# ProPrj_EPM_PCB.net
KiCad netlist of a schematic drawn in EasyEDA Pro
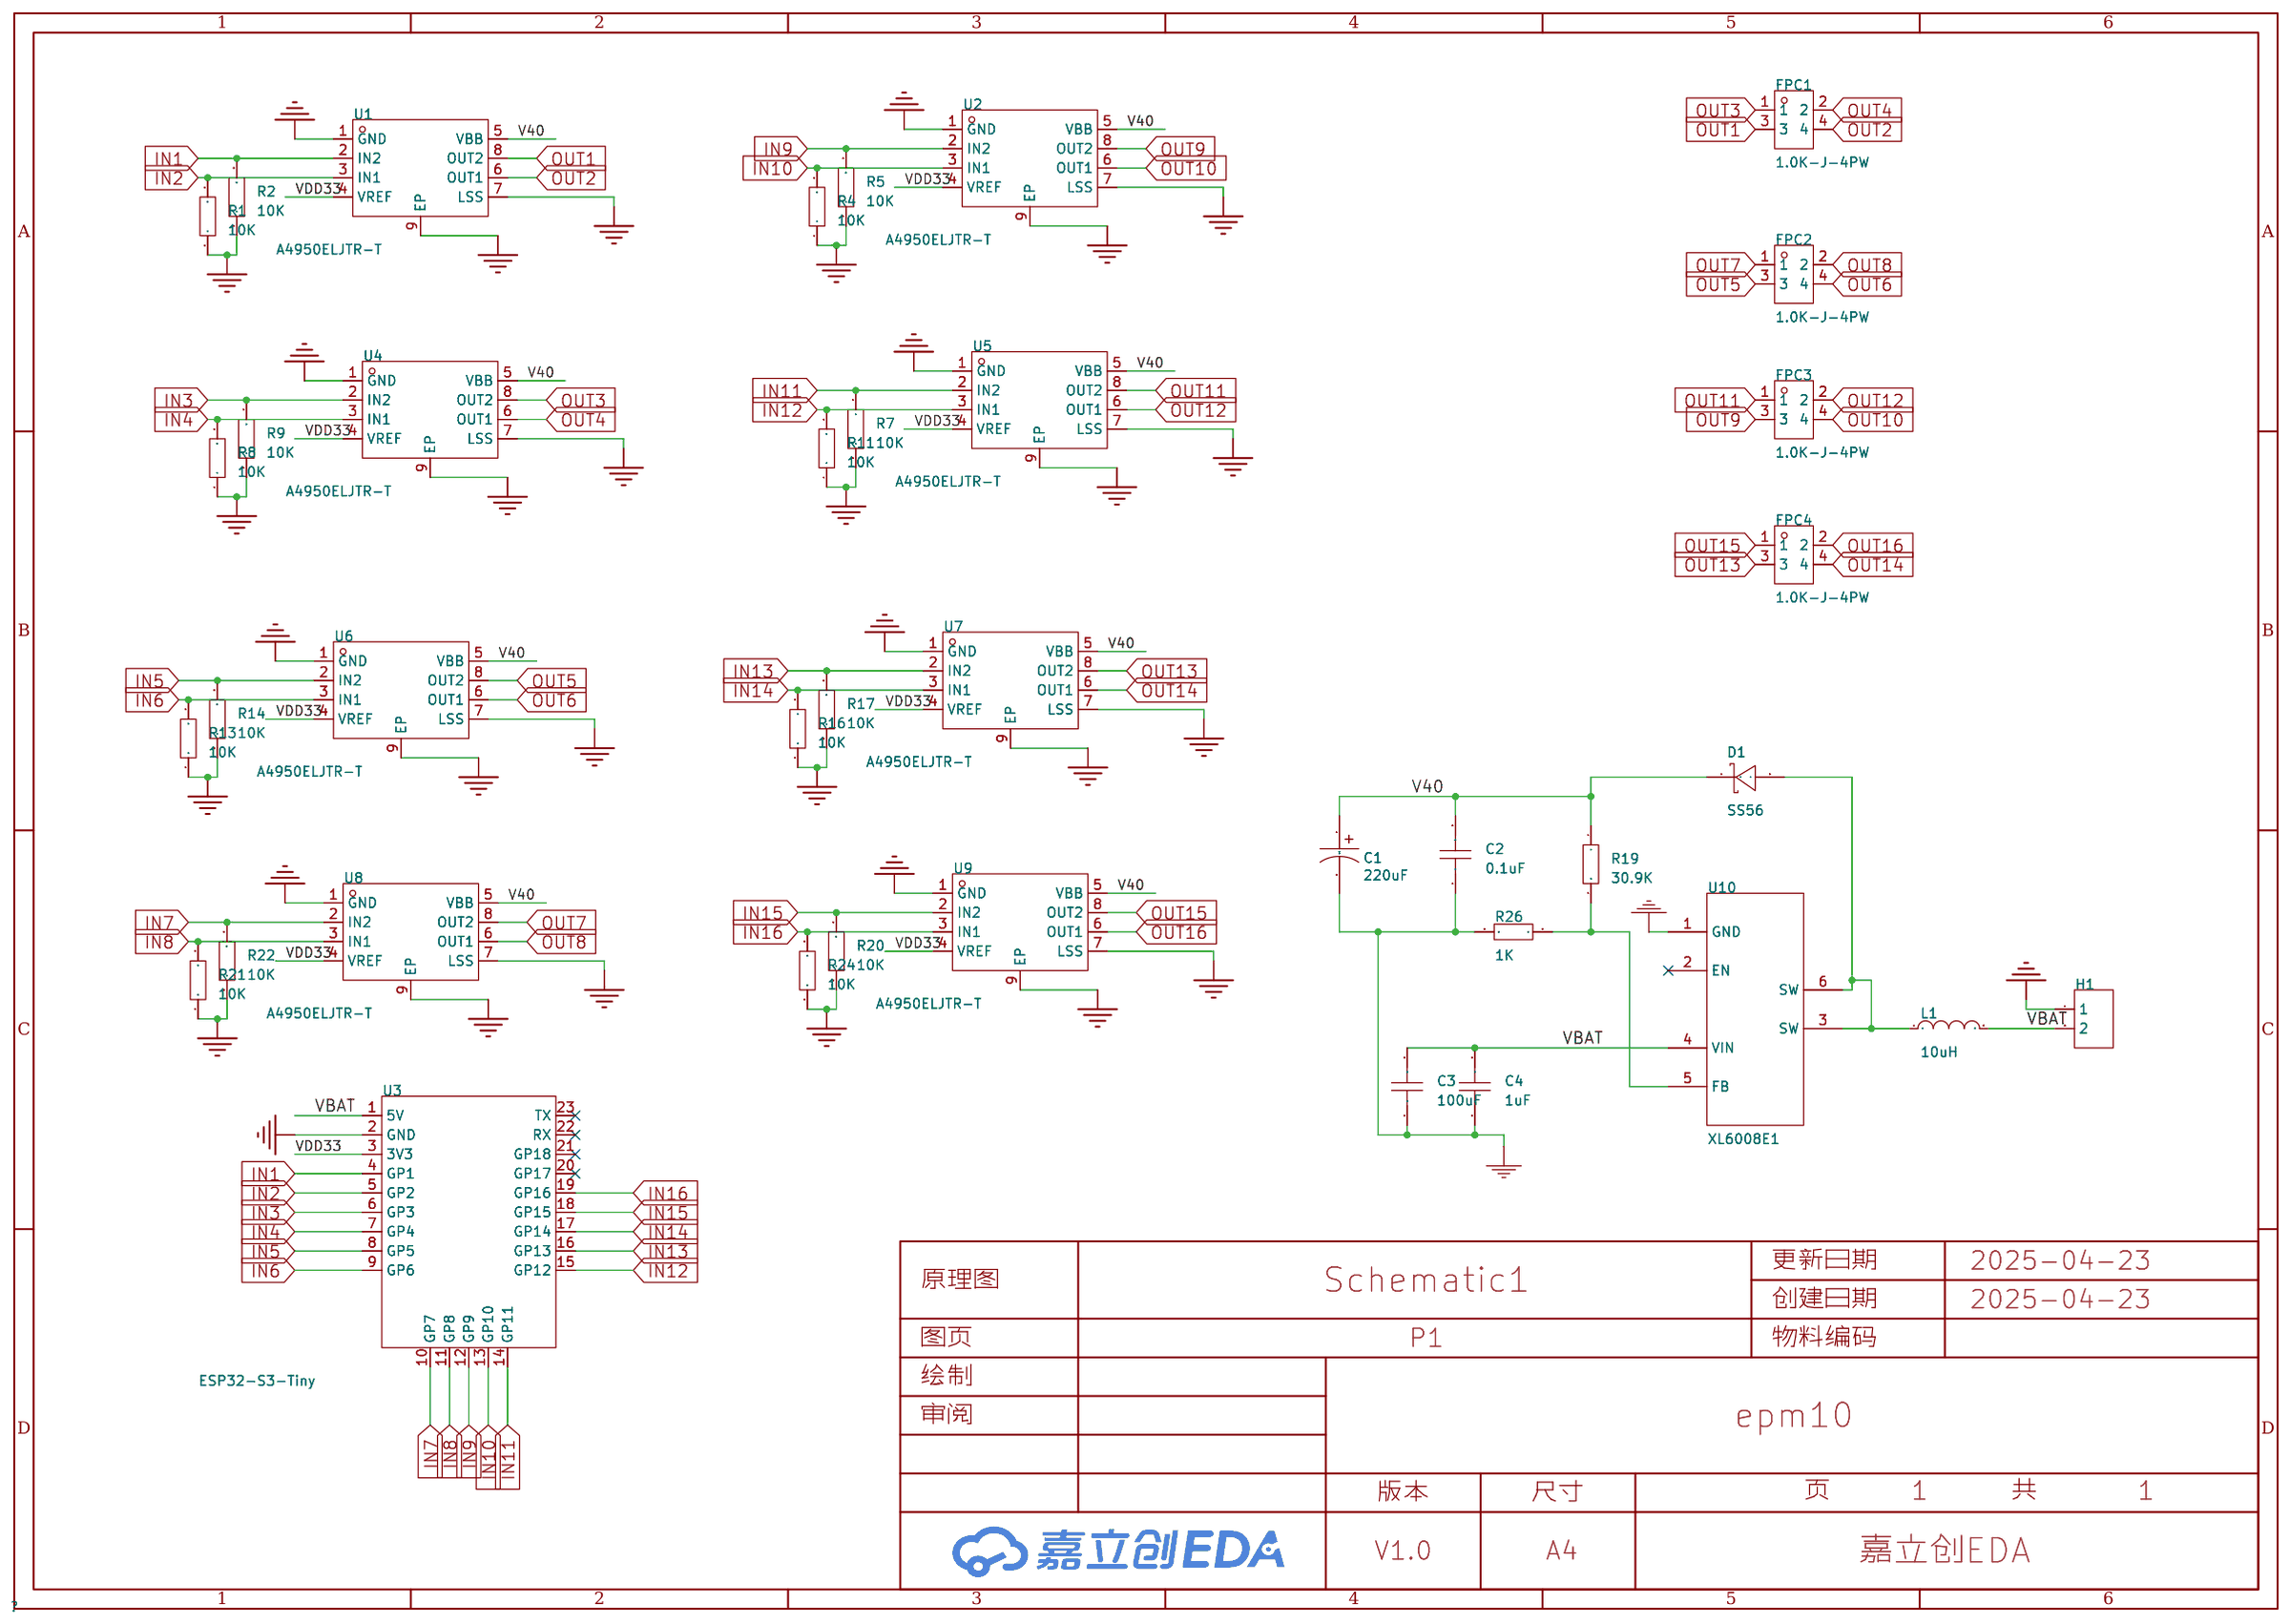
[diagram p0: schematic sheet]

(export (version "E")
  (design (tool "Eeschema 10.0.6"))
  (components
    (comp (ref "C1")
      (value "220uF")
      (footprint "easyedapro:CAP-TH_BD10.0-P5.00-D0.6-FD-A")
      (fields
        (field (name "Manufacturer Part") "SPZ1JM221G15O00RAXXX")
        (field (name "Manufacturer") "AISHI(艾华集团)")
      )
      (libsource (lib "easyedapro") (part "220uF"))
    )
    (comp (ref "C2")
      (value "0.1uF")
      (footprint "easyedapro:C0603")
      (libsource (lib "easyedapro") (part "CapAcitance"))
    )
    (comp (ref "C3")
      (value "100uF")
      (footprint "easyedapro:C1210")
      (description "容值:100uF;精度:±20%;额定电压:10V;材质(温度系数):X5R;")
      (fields
        (field (name "Manufacturer Part") "GRM32ER61A107ME20L")
        (field (name "Manufacturer") "muRata(村田)")
      )
      (libsource (lib "easyedapro") (part "GRM32ER61A107ME20L"))
    )
    (comp (ref "C4")
      (value "1uF")
      (footprint "easyedapro:C0603")
      (libsource (lib "easyedapro") (part "CapAcitance"))
    )
    (comp (ref "D1")
      (value "SS56")
      (footprint "easyedapro:SMA_L4.3-W2.6-LS5.2-RD")
      (description "二极管配置:独立式;正向压降(Vf):700mV@5A;直流反向耐压(Vr):60V;整流电流:5A;")
      (fields (field (name "Manufacturer") "MDD(辰达半导体)"))
      (libsource (lib "easyedapro") (part "SS56"))
    )
    (comp (ref "FPC1")
      (value "1.0K-J-4PW")
      (footprint "easyedapro:FPC-TH_4P-P1.00_HDGC_1.0K-J-4PW")
      (description "锁定特性:抽屉式;触点类型:下接;触点数量:4P;间距:1mm;安装类型:弯插;工作温度范围:-20°C~+85°C;")
      (fields (field (name "Manufacturer") "HDGC(华德共创)"))
      (libsource (lib "easyedapro") (part "1.0K-J-4PW"))
    )
    (comp (ref "FPC2")
      (value "1.0K-J-4PW")
      (footprint "easyedapro:FPC-TH_4P-P1.00_HDGC_1.0K-J-4PW")
      (description "锁定特性:抽屉式;触点类型:下接;触点数量:4P;间距:1mm;安装类型:弯插;工作温度范围:-20°C~+85°C;")
      (fields (field (name "Manufacturer") "HDGC(华德共创)"))
      (libsource (lib "easyedapro") (part "1.0K-J-4PW"))
    )
    (comp (ref "FPC3")
      (value "1.0K-J-4PW")
      (footprint "easyedapro:FPC-TH_4P-P1.00_HDGC_1.0K-J-4PW")
      (description "锁定特性:抽屉式;触点类型:下接;触点数量:4P;间距:1mm;安装类型:弯插;工作温度范围:-20°C~+85°C;")
      (fields (field (name "Manufacturer") "HDGC(华德共创)"))
      (libsource (lib "easyedapro") (part "1.0K-J-4PW"))
    )
    (comp (ref "FPC4")
      (value "1.0K-J-4PW")
      (footprint "easyedapro:FPC-TH_4P-P1.00_HDGC_1.0K-J-4PW")
      (description "锁定特性:抽屉式;触点类型:下接;触点数量:4P;间距:1mm;安装类型:弯插;工作温度范围:-20°C~+85°C;")
      (fields (field (name "Manufacturer") "HDGC(华德共创)"))
      (libsource (lib "easyedapro") (part "1.0K-J-4PW"))
    )
    (comp (ref "H1")
      (value "~")
      (footprint "easyedapro:HDR-TH_2P-P2.54-V-F")
      (libsource (lib "easyedapro") (part "Header-Female-2.54_1x2"))
    )
    (comp (ref "L1")
      (value "10uH")
      (footprint "easyedapro:IND-SMD_L3.0-W3.0_FTC303020D")
      (description "电感值:10uH;精度:±20%;额定电流:2.5A;饱和电流(Isat):3.8A;类型:一体成型电感;")
      (fields
        (field (name "Manufacturer Part") "FTC303020D100MBCA")
        (field (name "Manufacturer") "cjiang(长江微电)")
      )
      (libsource (lib "easyedapro") (part "FTC303020D100MBCA"))
    )
    (comp (ref "R1") (value "10K") (footprint "easyedapro:R0603") (libsource (lib "easyedapro") (part "电阻")))
    (comp (ref "R2") (value "10K") (footprint "easyedapro:R0603") (libsource (lib "easyedapro") (part "电阻")))
    (comp (ref "R4") (value "10K") (footprint "easyedapro:R0603") (libsource (lib "easyedapro") (part "电阻")))
    (comp (ref "R5") (value "10K") (footprint "easyedapro:R0603") (libsource (lib "easyedapro") (part "电阻")))
    (comp (ref "R7") (value "10K") (footprint "easyedapro:R0603") (libsource (lib "easyedapro") (part "电阻")))
    (comp (ref "R8") (value "10K") (footprint "easyedapro:R0603") (libsource (lib "easyedapro") (part "电阻")))
    (comp (ref "R9") (value "10K") (footprint "easyedapro:R0603") (libsource (lib "easyedapro") (part "电阻")))
    (comp (ref "R11") (value "10K") (footprint "easyedapro:R0603") (libsource (lib "easyedapro") (part "电阻")))
    (comp (ref "R13") (value "10K") (footprint "easyedapro:R0603") (libsource (lib "easyedapro") (part "电阻")))
    (comp (ref "R14") (value "10K") (footprint "easyedapro:R0603") (libsource (lib "easyedapro") (part "电阻")))
    (comp (ref "R16") (value "10K") (footprint "easyedapro:R0603") (libsource (lib "easyedapro") (part "电阻")))
    (comp (ref "R17") (value "10K") (footprint "easyedapro:R0603") (libsource (lib "easyedapro") (part "电阻")))
    (comp (ref "R19")
      (value "30.9K")
      (footprint "easyedapro:R0603")
      (libsource (lib "easyedapro") (part "电阻"))
    )
    (comp (ref "R20") (value "10K") (footprint "easyedapro:R0603") (libsource (lib "easyedapro") (part "电阻")))
    (comp (ref "R21") (value "10K") (footprint "easyedapro:R0603") (libsource (lib "easyedapro") (part "电阻")))
    (comp (ref "R22") (value "10K") (footprint "easyedapro:R0603") (libsource (lib "easyedapro") (part "电阻")))
    (comp (ref "R24") (value "10K") (footprint "easyedapro:R0603") (libsource (lib "easyedapro") (part "电阻")))
    (comp (ref "R26") (value "1K") (footprint "easyedapro:R0603") (libsource (lib "easyedapro") (part "电阻")))
    (comp (ref "U1")
      (value "A4950ELJTR-T")
      (footprint "easyedapro:ESOP-8_L4.9-W3.9-P1.27-LS6.0-BL-EP-1")
      (description "全桥DMOS PWM电机驱动器，直流有刷电机")
      (fields (field (name "Manufacturer") "JSMSEMI(杰盛微)"))
      (libsource (lib "easyedapro") (part "A4950ELJTR-T_C5804620"))
    )
    (comp (ref "U2")
      (value "A4950ELJTR-T")
      (footprint "easyedapro:ESOP-8_L4.9-W3.9-P1.27-LS6.0-BL-EP-1")
      (description "全桥DMOS PWM电机驱动器，直流有刷电机")
      (fields (field (name "Manufacturer") "JSMSEMI(杰盛微)"))
      (libsource (lib "easyedapro") (part "A4950ELJTR-T_C5804620"))
    )
    (comp (ref "U3")
      (value "ESP32-S3-Tiny")
      (footprint "easyedapro:COMM-SMD_23P-P2.54-L23.5-W18.0_ESP32-S3-TINY")
      (libsource (lib "easyedapro") (part "ESP32-S3-TINY"))
    )
    (comp (ref "U4")
      (value "A4950ELJTR-T")
      (footprint "easyedapro:ESOP-8_L4.9-W3.9-P1.27-LS6.0-BL-EP-1")
      (description "全桥DMOS PWM电机驱动器，直流有刷电机")
      (fields (field (name "Manufacturer") "JSMSEMI(杰盛微)"))
      (libsource (lib "easyedapro") (part "A4950ELJTR-T_C5804620"))
    )
    (comp (ref "U5")
      (value "A4950ELJTR-T")
      (footprint "easyedapro:ESOP-8_L4.9-W3.9-P1.27-LS6.0-BL-EP-1")
      (description "全桥DMOS PWM电机驱动器，直流有刷电机")
      (fields (field (name "Manufacturer") "JSMSEMI(杰盛微)"))
      (libsource (lib "easyedapro") (part "A4950ELJTR-T_C5804620"))
    )
    (comp (ref "U6")
      (value "A4950ELJTR-T")
      (footprint "easyedapro:ESOP-8_L4.9-W3.9-P1.27-LS6.0-BL-EP-1")
      (description "全桥DMOS PWM电机驱动器，直流有刷电机")
      (fields (field (name "Manufacturer") "JSMSEMI(杰盛微)"))
      (libsource (lib "easyedapro") (part "A4950ELJTR-T_C5804620"))
    )
    (comp (ref "U7")
      (value "A4950ELJTR-T")
      (footprint "easyedapro:ESOP-8_L4.9-W3.9-P1.27-LS6.0-BL-EP-1")
      (description "全桥DMOS PWM电机驱动器，直流有刷电机")
      (fields (field (name "Manufacturer") "JSMSEMI(杰盛微)"))
      (libsource (lib "easyedapro") (part "A4950ELJTR-T_C5804620"))
    )
    (comp (ref "U8")
      (value "A4950ELJTR-T")
      (footprint "easyedapro:ESOP-8_L4.9-W3.9-P1.27-LS6.0-BL-EP-1")
      (description "全桥DMOS PWM电机驱动器，直流有刷电机")
      (fields (field (name "Manufacturer") "JSMSEMI(杰盛微)"))
      (libsource (lib "easyedapro") (part "A4950ELJTR-T_C5804620"))
    )
    (comp (ref "U9")
      (value "A4950ELJTR-T")
      (footprint "easyedapro:ESOP-8_L4.9-W3.9-P1.27-LS6.0-BL-EP-1")
      (description "全桥DMOS PWM电机驱动器，直流有刷电机")
      (fields (field (name "Manufacturer") "JSMSEMI(杰盛微)"))
      (libsource (lib "easyedapro") (part "A4950ELJTR-T_C5804620"))
    )
    (comp (ref "U10")
      (value "XL6008E1")
      (footprint "easyedapro:TO-252-5_L6.6-W5.8-P1.27-TL")
      (description "功能类型:升降压型;输入电压:3.6V~32V;输出电流(最大值):3A;")
      (fields (field (name "Manufacturer") "XLSEMI(芯龙)"))
      (libsource (lib "easyedapro") (part "XL6008E1_C73012"))
    )
  )
  (nets
    (net (code "1") (name "/V40") (class "Default")
      (node (ref "C1") (pin "1") (pinfunction "1_1") (pintype "unspecified"))
      (node (ref "C2") (pin "2") (pinfunction "2_2") (pintype "input"))
      (node (ref "D1") (pin "1") (pinfunction "K_1") (pintype "unspecified"))
      (node (ref "R19") (pin "1") (pinfunction "1_1") (pintype "input"))
      (node (ref "U1") (pin "5") (pinfunction "VBB_5") (pintype "unspecified"))
      (node (ref "U2") (pin "5") (pinfunction "VBB_5") (pintype "unspecified"))
      (node (ref "U4") (pin "5") (pinfunction "VBB_5") (pintype "unspecified"))
      (node (ref "U5") (pin "5") (pinfunction "VBB_5") (pintype "unspecified"))
      (node (ref "U6") (pin "5") (pinfunction "VBB_5") (pintype "unspecified"))
      (node (ref "U7") (pin "5") (pinfunction "VBB_5") (pintype "unspecified"))
      (node (ref "U8") (pin "5") (pinfunction "VBB_5") (pintype "unspecified"))
      (node (ref "U9") (pin "5") (pinfunction "VBB_5") (pintype "unspecified"))
    )
    (net (code "2") (name "/VBAT") (class "Default")
      (node (ref "C3") (pin "2") (pinfunction "2_2") (pintype "unspecified"))
      (node (ref "C4") (pin "2") (pinfunction "2_2") (pintype "input"))
      (node (ref "H1") (pin "2") (pinfunction "2_2") (pintype "input"))
      (node (ref "L1") (pin "2") (pinfunction "2_2") (pintype "unspecified"))
      (node (ref "U10") (pin "4") (pinfunction "VIN_4") (pintype "unspecified"))
      (node (ref "U3") (pin "1") (pinfunction "5V_1") (pintype "unspecified"))
    )
    (net (code "3") (name "/VDD33") (class "Default")
      (node (ref "U1") (pin "4") (pinfunction "VREF_4") (pintype "unspecified"))
      (node (ref "U2") (pin "4") (pinfunction "VREF_4") (pintype "unspecified"))
      (node (ref "U3") (pin "3") (pinfunction "3V3_3") (pintype "unspecified"))
      (node (ref "U4") (pin "4") (pinfunction "VREF_4") (pintype "unspecified"))
      (node (ref "U5") (pin "4") (pinfunction "VREF_4") (pintype "unspecified"))
      (node (ref "U6") (pin "4") (pinfunction "VREF_4") (pintype "unspecified"))
      (node (ref "U7") (pin "4") (pinfunction "VREF_4") (pintype "unspecified"))
      (node (ref "U8") (pin "4") (pinfunction "VREF_4") (pintype "unspecified"))
      (node (ref "U9") (pin "4") (pinfunction "VREF_4") (pintype "unspecified"))
    )
    (net (code "4") (name "GND") (class "Default")
      (node (ref "C1") (pin "2") (pinfunction "2_2") (pintype "unspecified"))
      (node (ref "C2") (pin "1") (pinfunction "1_1") (pintype "input"))
      (node (ref "C3") (pin "1") (pinfunction "1_1") (pintype "unspecified"))
      (node (ref "C4") (pin "1") (pinfunction "1_1") (pintype "input"))
      (node (ref "H1") (pin "1") (pinfunction "1_1") (pintype "input"))
      (node (ref "R1") (pin "1") (pinfunction "1_1") (pintype "input"))
      (node (ref "R11") (pin "1") (pinfunction "1_1") (pintype "input"))
      (node (ref "R13") (pin "1") (pinfunction "1_1") (pintype "input"))
      (node (ref "R14") (pin "1") (pinfunction "1_1") (pintype "input"))
      (node (ref "R16") (pin "1") (pinfunction "1_1") (pintype "input"))
      (node (ref "R17") (pin "1") (pinfunction "1_1") (pintype "input"))
      (node (ref "R2") (pin "1") (pinfunction "1_1") (pintype "input"))
      (node (ref "R20") (pin "1") (pinfunction "1_1") (pintype "input"))
      (node (ref "R21") (pin "1") (pinfunction "1_1") (pintype "input"))
      (node (ref "R22") (pin "1") (pinfunction "1_1") (pintype "input"))
      (node (ref "R24") (pin "1") (pinfunction "1_1") (pintype "input"))
      (node (ref "R26") (pin "2") (pinfunction "2_2") (pintype "input"))
      (node (ref "R4") (pin "1") (pinfunction "1_1") (pintype "input"))
      (node (ref "R5") (pin "1") (pinfunction "1_1") (pintype "input"))
      (node (ref "R7") (pin "1") (pinfunction "1_1") (pintype "input"))
      (node (ref "R8") (pin "1") (pinfunction "1_1") (pintype "input"))
      (node (ref "R9") (pin "1") (pinfunction "1_1") (pintype "input"))
      (node (ref "U1") (pin "1") (pinfunction "GND_1") (pintype "unspecified"))
      (node (ref "U1") (pin "7") (pinfunction "LSS_7") (pintype "unspecified"))
      (node (ref "U1") (pin "9") (pinfunction "EP_9") (pintype "unspecified"))
      (node (ref "U10") (pin "1") (pinfunction "GND_1") (pintype "unspecified"))
      (node (ref "U2") (pin "1") (pinfunction "GND_1") (pintype "unspecified"))
      (node (ref "U2") (pin "7") (pinfunction "LSS_7") (pintype "unspecified"))
      (node (ref "U2") (pin "9") (pinfunction "EP_9") (pintype "unspecified"))
      (node (ref "U3") (pin "2") (pinfunction "GND_2") (pintype "unspecified"))
      (node (ref "U4") (pin "1") (pinfunction "GND_1") (pintype "unspecified"))
      (node (ref "U4") (pin "7") (pinfunction "LSS_7") (pintype "unspecified"))
      (node (ref "U4") (pin "9") (pinfunction "EP_9") (pintype "unspecified"))
      (node (ref "U5") (pin "1") (pinfunction "GND_1") (pintype "unspecified"))
      (node (ref "U5") (pin "7") (pinfunction "LSS_7") (pintype "unspecified"))
      (node (ref "U5") (pin "9") (pinfunction "EP_9") (pintype "unspecified"))
      (node (ref "U6") (pin "1") (pinfunction "GND_1") (pintype "unspecified"))
      (node (ref "U6") (pin "7") (pinfunction "LSS_7") (pintype "unspecified"))
      (node (ref "U6") (pin "9") (pinfunction "EP_9") (pintype "unspecified"))
      (node (ref "U7") (pin "1") (pinfunction "GND_1") (pintype "unspecified"))
      (node (ref "U7") (pin "7") (pinfunction "LSS_7") (pintype "unspecified"))
      (node (ref "U7") (pin "9") (pinfunction "EP_9") (pintype "unspecified"))
      (node (ref "U8") (pin "1") (pinfunction "GND_1") (pintype "unspecified"))
      (node (ref "U8") (pin "7") (pinfunction "LSS_7") (pintype "unspecified"))
      (node (ref "U8") (pin "9") (pinfunction "EP_9") (pintype "unspecified"))
      (node (ref "U9") (pin "1") (pinfunction "GND_1") (pintype "unspecified"))
      (node (ref "U9") (pin "7") (pinfunction "LSS_7") (pintype "unspecified"))
      (node (ref "U9") (pin "9") (pinfunction "EP_9") (pintype "unspecified"))
    )
    (net (code "5") (name "IN1") (class "Default")
      (node (ref "R2") (pin "2") (pinfunction "2_2") (pintype "input"))
      (node (ref "U1") (pin "2") (pinfunction "IN2_2") (pintype "unspecified"))
      (node (ref "U3") (pin "4") (pinfunction "GP1_4") (pintype "unspecified"))
    )
    (net (code "6") (name "IN2") (class "Default")
      (node (ref "R1") (pin "2") (pinfunction "2_2") (pintype "input"))
      (node (ref "U1") (pin "3") (pinfunction "IN1_3") (pintype "unspecified"))
      (node (ref "U3") (pin "5") (pinfunction "GP2_5") (pintype "unspecified"))
    )
    (net (code "7") (name "IN3") (class "Default")
      (node (ref "R9") (pin "2") (pinfunction "2_2") (pintype "input"))
      (node (ref "U3") (pin "6") (pinfunction "GP3_6") (pintype "unspecified"))
      (node (ref "U4") (pin "2") (pinfunction "IN2_2") (pintype "unspecified"))
    )
    (net (code "8") (name "IN4") (class "Default")
      (node (ref "R8") (pin "2") (pinfunction "2_2") (pintype "input"))
      (node (ref "U3") (pin "7") (pinfunction "GP4_7") (pintype "unspecified"))
      (node (ref "U4") (pin "3") (pinfunction "IN1_3") (pintype "unspecified"))
    )
    (net (code "9") (name "IN5") (class "Default")
      (node (ref "R14") (pin "2") (pinfunction "2_2") (pintype "input"))
      (node (ref "U3") (pin "8") (pinfunction "GP5_8") (pintype "unspecified"))
      (node (ref "U6") (pin "2") (pinfunction "IN2_2") (pintype "unspecified"))
    )
    (net (code "10") (name "IN6") (class "Default")
      (node (ref "R13") (pin "2") (pinfunction "2_2") (pintype "input"))
      (node (ref "U3") (pin "9") (pinfunction "GP6_9") (pintype "unspecified"))
      (node (ref "U6") (pin "3") (pinfunction "IN1_3") (pintype "unspecified"))
    )
    (net (code "11") (name "IN7") (class "Default")
      (node (ref "R22") (pin "2") (pinfunction "2_2") (pintype "input"))
      (node (ref "U3") (pin "10") (pinfunction "GP7_10") (pintype "unspecified"))
      (node (ref "U8") (pin "2") (pinfunction "IN2_2") (pintype "unspecified"))
    )
    (net (code "12") (name "IN8") (class "Default")
      (node (ref "R21") (pin "2") (pinfunction "2_2") (pintype "input"))
      (node (ref "U3") (pin "11") (pinfunction "GP8_11") (pintype "unspecified"))
      (node (ref "U8") (pin "3") (pinfunction "IN1_3") (pintype "unspecified"))
    )
    (net (code "13") (name "IN9") (class "Default")
      (node (ref "R5") (pin "2") (pinfunction "2_2") (pintype "input"))
      (node (ref "U2") (pin "2") (pinfunction "IN2_2") (pintype "unspecified"))
      (node (ref "U3") (pin "12") (pinfunction "GP9_12") (pintype "unspecified"))
    )
    (net (code "14") (name "IN10") (class "Default")
      (node (ref "R4") (pin "2") (pinfunction "2_2") (pintype "input"))
      (node (ref "U2") (pin "3") (pinfunction "IN1_3") (pintype "unspecified"))
      (node (ref "U3") (pin "13") (pinfunction "GP10_13") (pintype "unspecified"))
    )
    (net (code "15") (name "IN11") (class "Default")
      (node (ref "R7") (pin "2") (pinfunction "2_2") (pintype "input"))
      (node (ref "U3") (pin "14") (pinfunction "GP11_14") (pintype "unspecified"))
      (node (ref "U5") (pin "2") (pinfunction "IN2_2") (pintype "unspecified"))
    )
    (net (code "16") (name "IN12") (class "Default")
      (node (ref "R11") (pin "2") (pinfunction "2_2") (pintype "input"))
      (node (ref "U3") (pin "15") (pinfunction "GP12_15") (pintype "unspecified"))
      (node (ref "U5") (pin "3") (pinfunction "IN1_3") (pintype "unspecified"))
    )
    (net (code "17") (name "IN13") (class "Default")
      (node (ref "R17") (pin "2") (pinfunction "2_2") (pintype "input"))
      (node (ref "U3") (pin "16") (pinfunction "GP13_16") (pintype "unspecified"))
      (node (ref "U7") (pin "2") (pinfunction "IN2_2") (pintype "unspecified"))
    )
    (net (code "18") (name "IN14") (class "Default")
      (node (ref "R16") (pin "2") (pinfunction "2_2") (pintype "input"))
      (node (ref "U3") (pin "17") (pinfunction "GP14_17") (pintype "unspecified"))
      (node (ref "U7") (pin "3") (pinfunction "IN1_3") (pintype "unspecified"))
    )
    (net (code "19") (name "IN15") (class "Default")
      (node (ref "R20") (pin "2") (pinfunction "2_2") (pintype "input"))
      (node (ref "U3") (pin "18") (pinfunction "GP15_18") (pintype "unspecified"))
      (node (ref "U9") (pin "2") (pinfunction "IN2_2") (pintype "unspecified"))
    )
    (net (code "20") (name "IN16") (class "Default")
      (node (ref "R24") (pin "2") (pinfunction "2_2") (pintype "input"))
      (node (ref "U3") (pin "19") (pinfunction "GP16_19") (pintype "unspecified"))
      (node (ref "U9") (pin "3") (pinfunction "IN1_3") (pintype "unspecified"))
    )
    (net (code "21") (name "Net-(D1-A)") (class "Default")
      (node (ref "D1") (pin "2") (pinfunction "A_2") (pintype "unspecified"))
      (node (ref "L1") (pin "1") (pinfunction "1_1") (pintype "unspecified"))
      (node (ref "U10") (pin "3") (pinfunction "SW_3") (pintype "unspecified"))
      (node (ref "U10") (pin "6") (pinfunction "SW_6") (pintype "unspecified"))
    )
    (net (code "22") (name "Net-(U10-FB)") (class "Default")
      (node (ref "R19") (pin "2") (pinfunction "2_2") (pintype "input"))
      (node (ref "R26") (pin "1") (pinfunction "1_1") (pintype "input"))
      (node (ref "U10") (pin "5") (pinfunction "FB_5") (pintype "unspecified"))
    )
    (net (code "23") (name "OUT1") (class "Default")
      (node (ref "FPC1") (pin "3") (pinfunction "3_3") (pintype "unspecified"))
      (node (ref "U1") (pin "8") (pinfunction "OUT2_8") (pintype "unspecified"))
    )
    (net (code "24") (name "OUT2") (class "Default")
      (node (ref "FPC1") (pin "4") (pinfunction "4_4") (pintype "unspecified"))
      (node (ref "U1") (pin "6") (pinfunction "OUT1_6") (pintype "unspecified"))
    )
    (net (code "25") (name "OUT3") (class "Default")
      (node (ref "FPC1") (pin "1") (pinfunction "1_1") (pintype "unspecified"))
      (node (ref "U4") (pin "8") (pinfunction "OUT2_8") (pintype "unspecified"))
    )
    (net (code "26") (name "OUT4") (class "Default")
      (node (ref "FPC1") (pin "2") (pinfunction "2_2") (pintype "unspecified"))
      (node (ref "U4") (pin "6") (pinfunction "OUT1_6") (pintype "unspecified"))
    )
    (net (code "27") (name "OUT5") (class "Default")
      (node (ref "FPC2") (pin "3") (pinfunction "3_3") (pintype "unspecified"))
      (node (ref "U6") (pin "8") (pinfunction "OUT2_8") (pintype "unspecified"))
    )
    (net (code "28") (name "OUT6") (class "Default")
      (node (ref "FPC2") (pin "4") (pinfunction "4_4") (pintype "unspecified"))
      (node (ref "U6") (pin "6") (pinfunction "OUT1_6") (pintype "unspecified"))
    )
    (net (code "29") (name "OUT7") (class "Default")
      (node (ref "FPC2") (pin "1") (pinfunction "1_1") (pintype "unspecified"))
      (node (ref "U8") (pin "8") (pinfunction "OUT2_8") (pintype "unspecified"))
    )
    (net (code "30") (name "OUT8") (class "Default")
      (node (ref "FPC2") (pin "2") (pinfunction "2_2") (pintype "unspecified"))
      (node (ref "U8") (pin "6") (pinfunction "OUT1_6") (pintype "unspecified"))
    )
    (net (code "31") (name "OUT9") (class "Default")
      (node (ref "FPC3") (pin "3") (pinfunction "3_3") (pintype "unspecified"))
      (node (ref "U2") (pin "8") (pinfunction "OUT2_8") (pintype "unspecified"))
    )
    (net (code "32") (name "OUT10") (class "Default")
      (node (ref "FPC3") (pin "4") (pinfunction "4_4") (pintype "unspecified"))
      (node (ref "U2") (pin "6") (pinfunction "OUT1_6") (pintype "unspecified"))
    )
    (net (code "33") (name "OUT11") (class "Default")
      (node (ref "FPC3") (pin "1") (pinfunction "1_1") (pintype "unspecified"))
      (node (ref "U5") (pin "8") (pinfunction "OUT2_8") (pintype "unspecified"))
    )
    (net (code "34") (name "OUT12") (class "Default")
      (node (ref "FPC3") (pin "2") (pinfunction "2_2") (pintype "unspecified"))
      (node (ref "U5") (pin "6") (pinfunction "OUT1_6") (pintype "unspecified"))
    )
    (net (code "35") (name "OUT13") (class "Default")
      (node (ref "FPC4") (pin "3") (pinfunction "3_3") (pintype "unspecified"))
      (node (ref "U7") (pin "8") (pinfunction "OUT2_8") (pintype "unspecified"))
    )
    (net (code "36") (name "OUT14") (class "Default")
      (node (ref "FPC4") (pin "4") (pinfunction "4_4") (pintype "unspecified"))
      (node (ref "U7") (pin "6") (pinfunction "OUT1_6") (pintype "unspecified"))
    )
    (net (code "37") (name "OUT15") (class "Default")
      (node (ref "FPC4") (pin "1") (pinfunction "1_1") (pintype "unspecified"))
      (node (ref "U9") (pin "8") (pinfunction "OUT2_8") (pintype "unspecified"))
    )
    (net (code "38") (name "OUT16") (class "Default")
      (node (ref "FPC4") (pin "2") (pinfunction "2_2") (pintype "unspecified"))
      (node (ref "U9") (pin "6") (pinfunction "OUT1_6") (pintype "unspecified"))
    )
    (net (code "39") (name "unconnected-(U3-GP17-Pad20)") (class "Default")
      (node (ref "U3") (pin "20") (pinfunction "GP17_20") (pintype "unspecified+no_connect"))
    )
    (net (code "40") (name "unconnected-(U3-GP18-Pad21)") (class "Default")
      (node (ref "U3") (pin "21") (pinfunction "GP18_21") (pintype "unspecified+no_connect"))
    )
    (net (code "41") (name "unconnected-(U3-RX-Pad22)") (class "Default")
      (node (ref "U3") (pin "22") (pinfunction "RX_22") (pintype "unspecified+no_connect"))
    )
    (net (code "42") (name "unconnected-(U3-TX-Pad23)") (class "Default")
      (node (ref "U3") (pin "23") (pinfunction "TX_23") (pintype "unspecified+no_connect"))
    )
    (net (code "43") (name "unconnected-(U10-EN-Pad2)") (class "Default")
      (node (ref "U10") (pin "2") (pinfunction "EN_2") (pintype "unspecified+no_connect"))
    )
  )
)
